# qwiic_blower.net
KiCad netlist of a schematic drawn in EAGLE
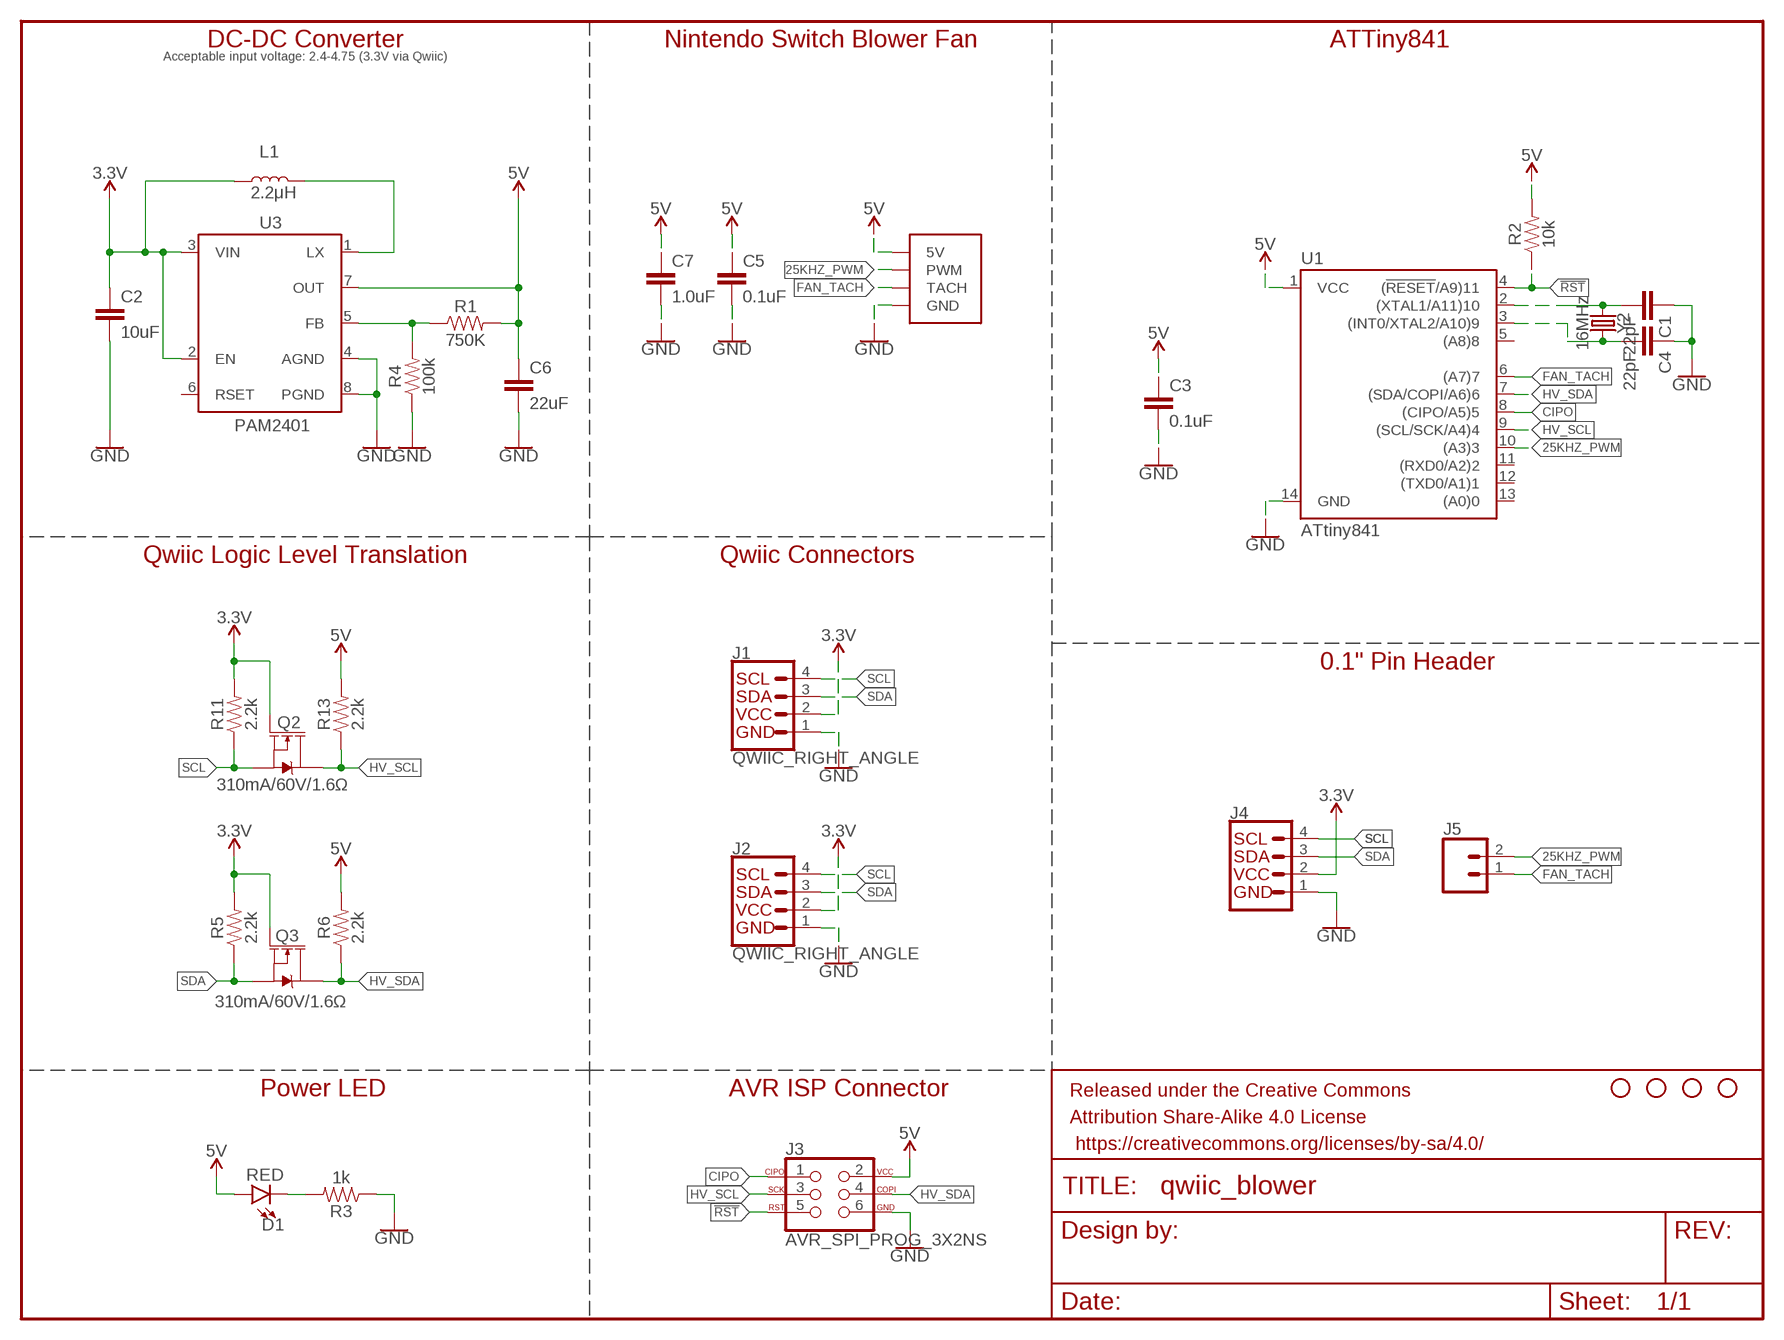
[diagram p0: schematic, sheet 1]

(export (version "E")
  (design (tool "Eeschema 10.0.6"))
  (components
    (comp (ref "C1")
      (value "22pF")
      (footprint "eagle-import:0603")
      (libsource (lib "eagle-import") (part "22PF-0603-50V-5%"))
    )
    (comp (ref "C2")
      (value "10uF")
      (footprint "eagle-import:0603")
      (libsource (lib "eagle-import") (part "10UF-0603-6.3V-20%"))
    )
    (comp (ref "C3")
      (value "0.1uF")
      (footprint "eagle-import:0603")
      (libsource (lib "eagle-import") (part "0.1UF-0603-25V-(+80/-20%)"))
    )
    (comp (ref "C4")
      (value "22pF")
      (footprint "eagle-import:0603")
      (libsource (lib "eagle-import") (part "22PF-0603-50V-5%"))
    )
    (comp (ref "C5")
      (value "0.1uF")
      (footprint "eagle-import:0603")
      (libsource (lib "eagle-import") (part "0.1UF-0603-25V-(+80/-20%)"))
    )
    (comp (ref "C6")
      (value "22uF")
      (footprint "eagle-import:0805")
      (libsource (lib "eagle-import") (part "22UF-0805-6.3V-20%"))
    )
    (comp (ref "C7")
      (value "1.0uF")
      (footprint "eagle-import:0603")
      (libsource (lib "eagle-import") (part "1.0UF-0603-16V-10%"))
    )
    (comp (ref "D1")
      (value "RED")
      (footprint "eagle-import:LED-0603")
      (libsource (lib "eagle-import") (part "LED-RED0603"))
    )
    (comp (ref "FRAME1")
      (value "FRAME-LETTER")
      (footprint "eagle-import:CREATIVE_COMMONS")
      (libsource (lib "eagle-import") (part "FRAME-LETTER"))
    )
    (comp (ref "H1")
      (value "STAND-OFF")
      (footprint "eagle-import:STAND-OFF")
      (libsource (lib "eagle-import") (part "STAND-OFF"))
    )
    (comp (ref "H2")
      (value "STAND-OFF")
      (footprint "eagle-import:STAND-OFF")
      (libsource (lib "eagle-import") (part "STAND-OFF"))
    )
    (comp (ref "H3")
      (value "STAND-OFF")
      (footprint "eagle-import:STAND-OFF")
      (libsource (lib "eagle-import") (part "STAND-OFF"))
    )
    (comp (ref "H4")
      (value "STAND-OFF")
      (footprint "eagle-import:STAND-OFF")
      (libsource (lib "eagle-import") (part "STAND-OFF"))
    )
    (comp (ref "J1")
      (value "QWIIC_RIGHT_ANGLE")
      (footprint "eagle-import:JST04_1MM_RA")
      (libsource (lib "eagle-import") (part "QWIIC_CONNECTORJS-1MM"))
    )
    (comp (ref "J2")
      (value "QWIIC_RIGHT_ANGLE")
      (footprint "eagle-import:JST04_1MM_RA")
      (libsource (lib "eagle-import") (part "QWIIC_CONNECTORJS-1MM"))
    )
    (comp (ref "J3")
      (value "AVR_SPI_PROG_3X2NS")
      (footprint "eagle-import:2X3-NS")
      (libsource (lib "eagle-import") (part "AVR_SPI_PROG_3X2NS"))
    )
    (comp (ref "J4")
      (value "I2C_STANDARD_NO_SILK")
      (footprint "eagle-import:1X04_NO_SILK")
      (libsource (lib "eagle-import") (part "I2C_STANDARD_NO_SILK"))
    )
    (comp (ref "J5")
      (value "CONN_021X02_NO_SILK")
      (footprint "eagle-import:1X02_NO_SILK")
      (libsource (lib "eagle-import") (part "CONN_021X02_NO_SILK"))
    )
    (comp (ref "L1")
      (value "2.2μH")
      (footprint "eagle-import:0806")
      (libsource (lib "eagle-import") (part "2.2μH_SHIELDED_INDUCTOR"))
    )
    (comp (ref "Q2")
      (value "310mA/60V/1.6Ω")
      (footprint "eagle-import:SOT323")
      (libsource (lib "eagle-import") (part "MOSFET-NCH-2N7002PW"))
    )
    (comp (ref "Q3")
      (value "310mA/60V/1.6Ω")
      (footprint "eagle-import:SOT323")
      (libsource (lib "eagle-import") (part "MOSFET-NCH-2N7002PW"))
    )
    (comp (ref "R1")
      (value "750K")
      (footprint "eagle-import:0603")
      (libsource (lib "eagle-import") (part "750KOHM-0603-1/10W-1%"))
    )
    (comp (ref "R2")
      (value "10k")
      (footprint "eagle-import:0603")
      (libsource (lib "eagle-import") (part "10KOHM-0603-1/10W-1%"))
    )
    (comp (ref "R3")
      (value "1k")
      (footprint "eagle-import:0603")
      (libsource (lib "eagle-import") (part "1KOHM-0603-1/10W-1%"))
    )
    (comp (ref "R4")
      (value "100k")
      (footprint "eagle-import:0603")
      (libsource (lib "eagle-import") (part "100KOHM-0603-1/10W-1%"))
    )
    (comp (ref "R5")
      (value "2.2k")
      (footprint "eagle-import:0603")
      (libsource (lib "eagle-import") (part "2.2KOHM-0603-1/10W-1%"))
    )
    (comp (ref "R6")
      (value "2.2k")
      (footprint "eagle-import:0603")
      (libsource (lib "eagle-import") (part "2.2KOHM-0603-1/10W-1%"))
    )
    (comp (ref "R11")
      (value "2.2k")
      (footprint "eagle-import:0603")
      (libsource (lib "eagle-import") (part "2.2KOHM-0603-1/10W-1%"))
    )
    (comp (ref "R13")
      (value "2.2k")
      (footprint "eagle-import:0603")
      (libsource (lib "eagle-import") (part "2.2KOHM-0603-1/10W-1%"))
    )
    (comp (ref "U$19")
      (value "NINTENDO_SWITCH_FAN")
      (footprint "eagle-import:FPC_4_0.5MM")
      (libsource (lib "eagle-import") (part "NINTENDO_SWITCH_FAN"))
    )
    (comp (ref "U1")
      (value "ATtiny841")
      (footprint "eagle-import:SO14")
      (libsource (lib "eagle-import") (part "ATTINY841-ARDUINO"))
    )
    (comp (ref "U3")
      (value "PAM2401")
      (footprint "eagle-import:MSOP8")
      (libsource (lib "eagle-import") (part "PAM2401"))
    )
    (comp (ref "Y2")
      (value "16MHz")
      (footprint "eagle-import:CRYSTAL-SMD-2.0X1.6MM")
      (libsource (lib "eagle-import") (part "CRYSTAL-16MHZSMD-2X1.6"))
    )
  )
  (nets
    (net (code "1") (name "/~{RST}") (class "Default")
      (node (ref "J3") (pin "5") (pinfunction "5_5") (pintype "passive"))
      (node (ref "R2") (pin "1") (pinfunction "1_1") (pintype "passive"))
      (node (ref "U1") (pin "4") (pinfunction "(~{RESET}/A9)11_4") (pintype "bidirectional"))
    )
    (net (code "2") (name "3.3V") (class "Default")
      (node (ref "C2") (pin "1") (pinfunction "1_1") (pintype "passive"))
      (node (ref "J1") (pin "2") (pinfunction "2_2") (pintype "power_in"))
      (node (ref "J2") (pin "2") (pinfunction "2_2") (pintype "power_in"))
      (node (ref "J4") (pin "2") (pinfunction "2_2") (pintype "power_in"))
      (node (ref "L1") (pin "1") (pinfunction "1_1") (pintype "passive"))
      (node (ref "Q2") (pin "1") (pinfunction "G_1") (pintype "bidirectional"))
      (node (ref "Q3") (pin "1") (pinfunction "G_1") (pintype "bidirectional"))
      (node (ref "R11") (pin "2") (pinfunction "2_2") (pintype "passive"))
      (node (ref "R5") (pin "2") (pinfunction "2_2") (pintype "passive"))
      (node (ref "U3") (pin "2") (pinfunction "EN_2") (pintype "bidirectional"))
      (node (ref "U3") (pin "3") (pinfunction "VIN_3") (pintype "bidirectional"))
    )
    (net (code "3") (name "5V") (class "Default")
      (node (ref "C3") (pin "1") (pinfunction "1_1") (pintype "passive"))
      (node (ref "C5") (pin "1") (pinfunction "1_1") (pintype "passive"))
      (node (ref "C6") (pin "1") (pinfunction "1_1") (pintype "passive"))
      (node (ref "C7") (pin "1") (pinfunction "1_1") (pintype "passive"))
      (node (ref "D1") (pin "A") (pinfunction "A_A") (pintype "passive"))
      (node (ref "J3") (pin "2") (pinfunction "2_2") (pintype "passive"))
      (node (ref "R1") (pin "2") (pinfunction "2_2") (pintype "passive"))
      (node (ref "R13") (pin "2") (pinfunction "2_2") (pintype "passive"))
      (node (ref "R2") (pin "2") (pinfunction "2_2") (pintype "passive"))
      (node (ref "R6") (pin "2") (pinfunction "2_2") (pintype "passive"))
      (node (ref "U$19") (pin "1") (pinfunction "5V_1") (pintype "power_in"))
      (node (ref "U1") (pin "1") (pinfunction "VCC_1") (pintype "power_in"))
      (node (ref "U3") (pin "7") (pinfunction "OUT_7") (pintype "bidirectional"))
    )
    (net (code "4") (name "25KHZ_PWM") (class "Default")
      (node (ref "J5") (pin "2") (pinfunction "2_2") (pintype "passive"))
      (node (ref "U$19") (pin "4") (pinfunction "PWM_4") (pintype "input"))
      (node (ref "U1") (pin "10") (pinfunction "(A3)3_10") (pintype "bidirectional"))
    )
    (net (code "5") (name "CIPO") (class "Default")
      (node (ref "J3") (pin "1") (pinfunction "1_1") (pintype "passive"))
      (node (ref "U1") (pin "8") (pinfunction "(CIPO/A5)5_8") (pintype "bidirectional"))
    )
    (net (code "6") (name "FAN_TACH") (class "Default")
      (node (ref "J5") (pin "1") (pinfunction "1_1") (pintype "passive"))
      (node (ref "U$19") (pin "2") (pinfunction "TACH_2") (pintype "output"))
      (node (ref "U1") (pin "6") (pinfunction "(A7)7_6") (pintype "bidirectional"))
    )
    (net (code "7") (name "GND") (class "Default")
      (node (ref "C1") (pin "1") (pinfunction "1_1") (pintype "passive"))
      (node (ref "C2") (pin "2") (pinfunction "2_2") (pintype "passive"))
      (node (ref "C3") (pin "2") (pinfunction "2_2") (pintype "passive"))
      (node (ref "C4") (pin "1") (pinfunction "1_1") (pintype "passive"))
      (node (ref "C5") (pin "2") (pinfunction "2_2") (pintype "passive"))
      (node (ref "C6") (pin "2") (pinfunction "2_2") (pintype "passive"))
      (node (ref "C7") (pin "2") (pinfunction "2_2") (pintype "passive"))
      (node (ref "J1") (pin "1") (pinfunction "1_1") (pintype "power_in"))
      (node (ref "J2") (pin "1") (pinfunction "1_1") (pintype "power_in"))
      (node (ref "J3") (pin "6") (pinfunction "6_6") (pintype "passive"))
      (node (ref "J4") (pin "1") (pinfunction "1_1") (pintype "power_in"))
      (node (ref "R3") (pin "1") (pinfunction "1_1") (pintype "passive"))
      (node (ref "R4") (pin "1") (pinfunction "1_1") (pintype "passive"))
      (node (ref "U$19") (pin "3") (pinfunction "GND_3") (pintype "bidirectional"))
      (node (ref "U1") (pin "14") (pinfunction "GND_14") (pintype "power_in"))
      (node (ref "U3") (pin "4") (pinfunction "AGND_4") (pintype "bidirectional"))
      (node (ref "U3") (pin "8") (pinfunction "PGND_8") (pintype "bidirectional"))
    )
    (net (code "8") (name "HV_SCL") (class "Default")
      (node (ref "J3") (pin "3") (pinfunction "3_3") (pintype "passive"))
      (node (ref "Q2") (pin "3") (pinfunction "D_3") (pintype "bidirectional"))
      (node (ref "R13") (pin "1") (pinfunction "1_1") (pintype "passive"))
      (node (ref "U1") (pin "9") (pinfunction "(SCL/SCK/A4)4_9") (pintype "bidirectional"))
    )
    (net (code "9") (name "HV_SDA") (class "Default")
      (node (ref "J3") (pin "4") (pinfunction "4_4") (pintype "passive"))
      (node (ref "Q3") (pin "3") (pinfunction "D_3") (pintype "bidirectional"))
      (node (ref "R6") (pin "1") (pinfunction "1_1") (pintype "passive"))
      (node (ref "U1") (pin "7") (pinfunction "(SDA/COPI/A6)6_7") (pintype "bidirectional"))
    )
    (net (code "10") (name "Net-(D1-PadC)") (class "Default")
      (node (ref "D1") (pin "C") (pinfunction "C_C") (pintype "passive"))
      (node (ref "R3") (pin "2") (pinfunction "2_2") (pintype "passive"))
    )
    (net (code "11") (name "Net-(U1-(INT0{slash}XTAL2{slash}A10)9)") (class "Default")
      (node (ref "C4") (pin "2") (pinfunction "2_2") (pintype "passive"))
      (node (ref "U1") (pin "3") (pinfunction "(INT0/XTAL2/A10)9_3") (pintype "bidirectional"))
      (node (ref "Y2") (pin "1") (pinfunction "1_1") (pintype "passive"))
    )
    (net (code "12") (name "Net-(U1-(XTAL1{slash}A11)10)") (class "Default")
      (node (ref "C1") (pin "2") (pinfunction "2_2") (pintype "passive"))
      (node (ref "U1") (pin "2") (pinfunction "(XTAL1/A11)10_2") (pintype "bidirectional"))
      (node (ref "Y2") (pin "3") (pinfunction "2_3") (pintype "passive"))
    )
    (net (code "13") (name "Net-(U3-FB)") (class "Default")
      (node (ref "R1") (pin "1") (pinfunction "1_1") (pintype "passive"))
      (node (ref "R4") (pin "2") (pinfunction "2_2") (pintype "passive"))
      (node (ref "U3") (pin "5") (pinfunction "FB_5") (pintype "bidirectional"))
    )
    (net (code "14") (name "Net-(U3-LX)") (class "Default")
      (node (ref "L1") (pin "2") (pinfunction "2_2") (pintype "passive"))
      (node (ref "U3") (pin "1") (pinfunction "LX_1") (pintype "bidirectional"))
    )
    (net (code "15") (name "SCL") (class "Default")
      (node (ref "J1") (pin "4") (pinfunction "4_4") (pintype "passive"))
      (node (ref "J2") (pin "4") (pinfunction "4_4") (pintype "passive"))
      (node (ref "J4") (pin "4") (pinfunction "4_4") (pintype "passive"))
      (node (ref "Q2") (pin "2") (pinfunction "S_2") (pintype "bidirectional"))
      (node (ref "R11") (pin "1") (pinfunction "1_1") (pintype "passive"))
    )
    (net (code "16") (name "SDA") (class "Default")
      (node (ref "J1") (pin "3") (pinfunction "3_3") (pintype "passive"))
      (node (ref "J2") (pin "3") (pinfunction "3_3") (pintype "passive"))
      (node (ref "J4") (pin "3") (pinfunction "3_3") (pintype "passive"))
      (node (ref "Q3") (pin "2") (pinfunction "S_2") (pintype "bidirectional"))
      (node (ref "R5") (pin "1") (pinfunction "1_1") (pintype "passive"))
    )
    (net (code "17") (name "unconnected-(U1-(A0)0-Pad13)") (class "Default")
      (node (ref "U1") (pin "13") (pinfunction "(A0)0_13") (pintype "bidirectional"))
    )
    (net (code "18") (name "unconnected-(U1-(A8)8-Pad5)") (class "Default")
      (node (ref "U1") (pin "5") (pinfunction "(A8)8_5") (pintype "bidirectional"))
    )
    (net (code "19") (name "unconnected-(U1-(RXD0{slash}A2)2-Pad11)") (class "Default")
      (node (ref "U1") (pin "11") (pinfunction "(RXD0/A2)2_11") (pintype "bidirectional"))
    )
    (net (code "20") (name "unconnected-(U1-(TXD0{slash}A1)1-Pad12)") (class "Default")
      (node (ref "U1") (pin "12") (pinfunction "(TXD0/A1)1_12") (pintype "bidirectional"))
    )
    (net (code "21") (name "unconnected-(U3-RSET-Pad6)") (class "Default")
      (node (ref "U3") (pin "6") (pinfunction "RSET_6") (pintype "bidirectional"))
    )
  )
)
